# TP_Integrador_Palomino_Villafane_Manuel_.net
KiCad netlist of a schematic drawn in Altium Designer
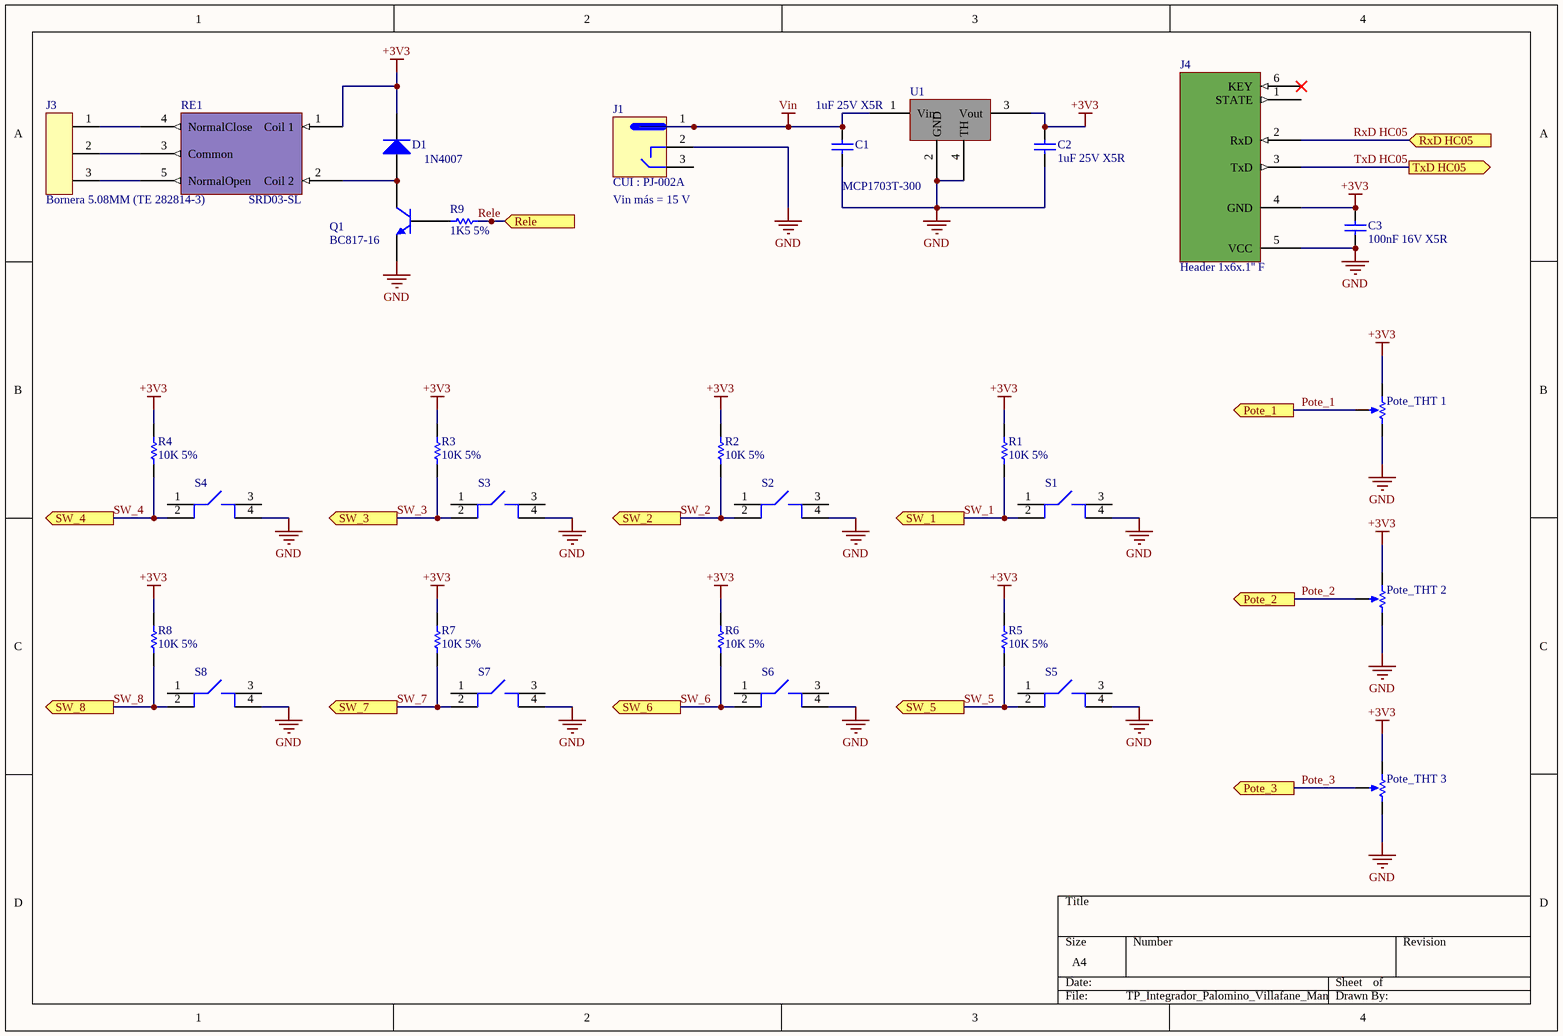
[diagram p0: TP_Integrador_Palomino_Villafane_Manuel_Per_R00.SchDoc]

(export (version "E")
  (design (tool "Eeschema 10.0.6"))
  (components
    (comp (ref "C1")
      (value "1uF 25V X5R")
      (footprint "C_0805")
      (description "Capacitor")
      (libsource (lib "Simulation Generic Components") (part "Capacitor"))
    )
    (comp (ref "C2")
      (value "1uF 25V X5R")
      (footprint "C_0805")
      (description "Capacitor")
      (libsource (lib "Simulation Generic Components") (part "Capacitor"))
    )
    (comp (ref "C3")
      (value "100nF 16V X5R")
      (footprint "C_0805")
      (description "Capacitor")
      (libsource (lib "Simulation Generic Components") (part "Capacitor"))
    )
    (comp (ref "D1")
      (value "1N4007")
      (footprint "SOD_123")
      (description "Diode")
      (libsource (lib "Simulation Generic Components") (part "Diode"))
    )
    (comp (ref "J1")
      (value "CUI : PJ-002A")
      (footprint "PJ002B")
      (description "DC Power Jack")
      (libsource (lib "Base_board_LPC845_R00") (part "PowerInput"))
    )
    (comp (ref "J3")
      (value "Bornera 5.08MM (TE 282814-3)")
      (footprint "BORNERA-3X 5.08MM")
      (description "Header")
      (libsource (lib "Base_board_LPC845_R00") (part "Header 1x3"))
    )
    (comp (ref "J4")
      (value "Header 1x6x.1'' F")
      (footprint "HEADER F 1x6 .1\" Horizintal")
      (description "Bluetooth")
      (libsource (lib "Base_board_LPC845_R00") (part "HC05"))
    )
    (comp (ref "Pote_THT 1")
      (value "Potentiometer")
      (footprint "POTE_9.5MM_PTV09")
      (libsource (lib "Simulation Generic Components") (part "Potentiometer"))
    )
    (comp (ref "Pote_THT 2")
      (value "Potentiometer")
      (footprint "POTE_9.5MM_PTV09")
      (libsource (lib "Simulation Generic Components") (part "Potentiometer"))
    )
    (comp (ref "Pote_THT 3")
      (value "Potentiometer")
      (footprint "POTE_9.5MM_PTV09")
      (libsource (lib "Simulation Generic Components") (part "Potentiometer"))
    )
    (comp (ref "Q1")
      (value "BC817-16")
      (footprint "SOT_23")
      (description "Bipolar NPN 3 Pins Transistor VBIC Model")
      (libsource (lib "Base_board_LPC845_R00") (part "BJT NPN VBIC"))
    )
    (comp (ref "R1")
      (value "10K 5%")
      (footprint "R_0805")
      (description "Resistor")
      (fields (field (name "Comment") "1K3 5%"))
      (libsource (lib "Simulation Generic Components") (part "Resistor"))
    )
    (comp (ref "R2")
      (value "10K 5%")
      (footprint "R_0805")
      (description "Resistor")
      (fields (field (name "Comment") "1K3 5%"))
      (libsource (lib "Simulation Generic Components") (part "Resistor"))
    )
    (comp (ref "R3")
      (value "10K 5%")
      (footprint "R_0805")
      (description "Resistor")
      (fields (field (name "Comment") "1K3 5%"))
      (libsource (lib "Simulation Generic Components") (part "Resistor"))
    )
    (comp (ref "R4")
      (value "10K 5%")
      (footprint "R_0805")
      (description "Resistor")
      (fields (field (name "Comment") "1K3 5%"))
      (libsource (lib "Simulation Generic Components") (part "Resistor"))
    )
    (comp (ref "R5")
      (value "10K 5%")
      (footprint "R_0805")
      (description "Resistor")
      (fields (field (name "Comment") "1K3 5%"))
      (libsource (lib "Simulation Generic Components") (part "Resistor"))
    )
    (comp (ref "R6")
      (value "10K 5%")
      (footprint "R_0805")
      (description "Resistor")
      (fields (field (name "Comment") "1K3 5%"))
      (libsource (lib "Simulation Generic Components") (part "Resistor"))
    )
    (comp (ref "R7")
      (value "10K 5%")
      (footprint "R_0805")
      (description "Resistor")
      (fields (field (name "Comment") "1K3 5%"))
      (libsource (lib "Simulation Generic Components") (part "Resistor"))
    )
    (comp (ref "R8")
      (value "10K 5%")
      (footprint "R_0805")
      (description "Resistor")
      (fields (field (name "Comment") "1K3 5%"))
      (libsource (lib "Simulation Generic Components") (part "Resistor"))
    )
    (comp (ref "R9")
      (value "Resistor")
      (footprint "R_0805")
      (fields (field (name "1K5 5%") "1K5 5%"))
      (libsource (lib "Simulation Generic Components") (part "Resistor"))
    )
    (comp (ref "RE1")
      (value "SRD03-SL")
      (footprint "Relay SRD")
      (description "Relay")
      (libsource (lib "Base_board_LPC845_R00") (part "RELAY"))
    )
    (comp (ref "S1")
      (value "Tact Switch - 430476085716")
      (footprint "Tact_Switch_12x12")
      (description "Tact Switch")
      (libsource (lib "*") (part "TactSwitch"))
    )
    (comp (ref "S2")
      (value "Tact Switch - 430476085716")
      (footprint "Tact_Switch_12x12")
      (description "Tact Switch")
      (libsource (lib "*") (part "TactSwitch"))
    )
    (comp (ref "S3")
      (value "Tact Switch - 430476085716")
      (footprint "Tact_Switch_12x12")
      (description "Tact Switch")
      (libsource (lib "*") (part "TactSwitch"))
    )
    (comp (ref "S4")
      (value "Tact Switch - 430476085716")
      (footprint "Tact_Switch_12x12")
      (description "Tact Switch")
      (libsource (lib "*") (part "TactSwitch"))
    )
    (comp (ref "S5")
      (value "Tact Switch - 430476085716")
      (footprint "Tact_Switch_12x12")
      (description "Tact Switch")
      (libsource (lib "*") (part "TactSwitch"))
    )
    (comp (ref "S6")
      (value "Tact Switch - 430476085716")
      (footprint "Tact_Switch_12x12")
      (description "Tact Switch")
      (libsource (lib "*") (part "TactSwitch"))
    )
    (comp (ref "S7")
      (value "Tact Switch - 430476085716")
      (footprint "Tact_Switch_12x12")
      (description "Tact Switch")
      (libsource (lib "*") (part "TactSwitch"))
    )
    (comp (ref "S8")
      (value "Tact Switch - 430476085716")
      (footprint "Tact_Switch_12x12")
      (description "Tact Switch")
      (libsource (lib "*") (part "TactSwitch"))
    )
    (comp (ref "U1")
      (value "MCP1703T-300")
      (footprint "SOT_223_4L")
      (description "LDO")
      (libsource (lib "Base_board_LPC845_R00") (part "MCP1703"))
    )
  )
  (nets
    (net (code "1") (name "+3V3") (class "Default")
      (node (ref "C2") (pin "2") (pinfunction "2_2") (pintype "passive"))
      (node (ref "C3") (pin "2") (pinfunction "2_2") (pintype "passive"))
      (node (ref "D1") (pin "2") (pinfunction "K_2") (pintype "passive"))
      (node (ref "J4") (pin "4") (pinfunction "GND_4") (pintype "power_in"))
      (node (ref "Pote_THT 1") (pin "1") (pinfunction "TOP_1") (pintype "passive"))
      (node (ref "Pote_THT 2") (pin "1") (pinfunction "TOP_1") (pintype "passive"))
      (node (ref "Pote_THT 3") (pin "1") (pinfunction "TOP_1") (pintype "passive"))
      (node (ref "R1") (pin "2") (pinfunction "2_2") (pintype "passive"))
      (node (ref "R2") (pin "2") (pinfunction "2_2") (pintype "passive"))
      (node (ref "R3") (pin "2") (pinfunction "2_2") (pintype "passive"))
      (node (ref "R4") (pin "2") (pinfunction "2_2") (pintype "passive"))
      (node (ref "R5") (pin "2") (pinfunction "2_2") (pintype "passive"))
      (node (ref "R6") (pin "2") (pinfunction "2_2") (pintype "passive"))
      (node (ref "R7") (pin "2") (pinfunction "2_2") (pintype "passive"))
      (node (ref "R8") (pin "2") (pinfunction "2_2") (pintype "passive"))
      (node (ref "RE1") (pin "1") (pinfunction "Coil_1_1") (pintype "input"))
      (node (ref "U1") (pin "3") (pinfunction "Vout_3") (pintype "power_in"))
    )
    (net (code "2") (name "/Pote_1") (class "Default")
      (node (ref "Pote_THT 1") (pin "3") (pinfunction "TAP_3") (pintype "passive"))
    )
    (net (code "3") (name "/Pote_2") (class "Default")
      (node (ref "Pote_THT 2") (pin "3") (pinfunction "TAP_3") (pintype "passive"))
    )
    (net (code "4") (name "/Pote_3") (class "Default")
      (node (ref "Pote_THT 3") (pin "3") (pinfunction "TAP_3") (pintype "passive"))
    )
    (net (code "5") (name "/Rele") (class "Default")
      (node (ref "R9") (pin "2") (pinfunction "2_2") (pintype "passive"))
    )
    (net (code "6") (name "/RxD HC05") (class "Default")
      (node (ref "J4") (pin "2") (pinfunction "RxD_2") (pintype "input"))
    )
    (net (code "7") (name "/SW_1") (class "Default")
      (node (ref "R1") (pin "1") (pinfunction "1_1") (pintype "passive"))
      (node (ref "S1") (pin "2") (pinfunction "2_2") (pintype "passive"))
    )
    (net (code "8") (name "/SW_2") (class "Default")
      (node (ref "R2") (pin "1") (pinfunction "1_1") (pintype "passive"))
      (node (ref "S2") (pin "2") (pinfunction "2_2") (pintype "passive"))
    )
    (net (code "9") (name "/SW_3") (class "Default")
      (node (ref "R3") (pin "1") (pinfunction "1_1") (pintype "passive"))
      (node (ref "S3") (pin "2") (pinfunction "2_2") (pintype "passive"))
    )
    (net (code "10") (name "/SW_4") (class "Default")
      (node (ref "R4") (pin "1") (pinfunction "1_1") (pintype "passive"))
      (node (ref "S4") (pin "2") (pinfunction "2_2") (pintype "passive"))
    )
    (net (code "11") (name "/SW_5") (class "Default")
      (node (ref "R5") (pin "1") (pinfunction "1_1") (pintype "passive"))
      (node (ref "S5") (pin "2") (pinfunction "2_2") (pintype "passive"))
    )
    (net (code "12") (name "/SW_6") (class "Default")
      (node (ref "R6") (pin "1") (pinfunction "1_1") (pintype "passive"))
      (node (ref "S6") (pin "2") (pinfunction "2_2") (pintype "passive"))
    )
    (net (code "13") (name "/SW_7") (class "Default")
      (node (ref "R7") (pin "1") (pinfunction "1_1") (pintype "passive"))
      (node (ref "S7") (pin "2") (pinfunction "2_2") (pintype "passive"))
    )
    (net (code "14") (name "/SW_8") (class "Default")
      (node (ref "R8") (pin "1") (pinfunction "1_1") (pintype "passive"))
      (node (ref "S8") (pin "2") (pinfunction "2_2") (pintype "passive"))
    )
    (net (code "15") (name "/TxD HC05") (class "Default")
      (node (ref "J4") (pin "3") (pinfunction "TxD_3") (pintype "output"))
    )
    (net (code "16") (name "GND") (class "Default")
      (node (ref "C1") (pin "1") (pinfunction "1_1") (pintype "passive"))
      (node (ref "C2") (pin "1") (pinfunction "1_1") (pintype "passive"))
      (node (ref "C3") (pin "1") (pinfunction "1_1") (pintype "passive"))
      (node (ref "J1") (pin "2") (pinfunction "2_2") (pintype "passive"))
      (node (ref "J4") (pin "5") (pinfunction "VCC_5") (pintype "power_in"))
      (node (ref "Pote_THT 1") (pin "2") (pinfunction "BOT_2") (pintype "passive"))
      (node (ref "Pote_THT 2") (pin "2") (pinfunction "BOT_2") (pintype "passive"))
      (node (ref "Pote_THT 3") (pin "2") (pinfunction "BOT_2") (pintype "passive"))
      (node (ref "Q1") (pin "2") (pinfunction "E_2") (pintype "passive"))
      (node (ref "S1") (pin "4") (pinfunction "4_4") (pintype "passive"))
      (node (ref "S2") (pin "4") (pinfunction "4_4") (pintype "passive"))
      (node (ref "S3") (pin "4") (pinfunction "4_4") (pintype "passive"))
      (node (ref "S4") (pin "4") (pinfunction "4_4") (pintype "passive"))
      (node (ref "S5") (pin "4") (pinfunction "4_4") (pintype "passive"))
      (node (ref "S6") (pin "4") (pinfunction "4_4") (pintype "passive"))
      (node (ref "S7") (pin "4") (pinfunction "4_4") (pintype "passive"))
      (node (ref "S8") (pin "4") (pinfunction "4_4") (pintype "passive"))
      (node (ref "U1") (pin "2") (pinfunction "GND_2") (pintype "power_in"))
      (node (ref "U1") (pin "4") (pinfunction "TH_4") (pintype "passive"))
    )
    (net (code "17") (name "Net-(D1-A)") (class "Default")
      (node (ref "D1") (pin "1") (pinfunction "A_1") (pintype "passive"))
      (node (ref "Q1") (pin "3") (pinfunction "C_3") (pintype "passive"))
      (node (ref "RE1") (pin "2") (pinfunction "Coil_2_2") (pintype "input"))
    )
    (net (code "18") (name "Net-(Q1-B)") (class "Default")
      (node (ref "Q1") (pin "1") (pinfunction "B_1") (pintype "passive"))
      (node (ref "R9") (pin "1") (pinfunction "1_1") (pintype "passive"))
    )
    (net (code "19") (name "Net-(RE1-Common)") (class "Default")
      (node (ref "J3") (pin "2") (pinfunction "2_2") (pintype "passive"))
      (node (ref "RE1") (pin "3") (pinfunction "Common_3") (pintype "output"))
    )
    (net (code "20") (name "Net-(RE1-NormalClose)") (class "Default")
      (node (ref "J3") (pin "1") (pinfunction "1_1") (pintype "passive"))
      (node (ref "RE1") (pin "4") (pinfunction "NormalClose_4") (pintype "output"))
    )
    (net (code "21") (name "Net-(RE1-NormalOpen)") (class "Default")
      (node (ref "J3") (pin "3") (pinfunction "3_3") (pintype "passive"))
      (node (ref "RE1") (pin "5") (pinfunction "NormalOpen_5") (pintype "output"))
    )
    (net (code "22") (name "Vin") (class "Default")
      (node (ref "C1") (pin "2") (pinfunction "2_2") (pintype "passive"))
      (node (ref "J1") (pin "1") (pinfunction "1_1") (pintype "passive"))
      (node (ref "U1") (pin "1") (pinfunction "Vin_1") (pintype "power_in"))
    )
    (net (code "23") (name "unconnected-(J1-Pad3)") (class "Default")
      (node (ref "J1") (pin "3") (pinfunction "3_3") (pintype "passive"))
    )
    (net (code "24") (name "unconnected-(J4-KEY-Pad6)") (class "Default")
      (node (ref "J4") (pin "6") (pinfunction "KEY_6") (pintype "input+no_connect"))
    )
    (net (code "25") (name "unconnected-(J4-STATE-Pad1)") (class "Default")
      (node (ref "J4") (pin "1") (pinfunction "STATE_1") (pintype "output"))
    )
    (net (code "26") (name "unconnected-(S1-Pad1)") (class "Default")
      (node (ref "S1") (pin "1") (pinfunction "1_1") (pintype "passive"))
    )
    (net (code "27") (name "unconnected-(S1-Pad3)") (class "Default")
      (node (ref "S1") (pin "3") (pinfunction "3_3") (pintype "passive"))
    )
    (net (code "28") (name "unconnected-(S2-Pad1)") (class "Default")
      (node (ref "S2") (pin "1") (pinfunction "1_1") (pintype "passive"))
    )
    (net (code "29") (name "unconnected-(S2-Pad3)") (class "Default")
      (node (ref "S2") (pin "3") (pinfunction "3_3") (pintype "passive"))
    )
    (net (code "30") (name "unconnected-(S3-Pad1)") (class "Default")
      (node (ref "S3") (pin "1") (pinfunction "1_1") (pintype "passive"))
    )
    (net (code "31") (name "unconnected-(S3-Pad3)") (class "Default")
      (node (ref "S3") (pin "3") (pinfunction "3_3") (pintype "passive"))
    )
    (net (code "32") (name "unconnected-(S4-Pad1)") (class "Default")
      (node (ref "S4") (pin "1") (pinfunction "1_1") (pintype "passive"))
    )
    (net (code "33") (name "unconnected-(S4-Pad3)") (class "Default")
      (node (ref "S4") (pin "3") (pinfunction "3_3") (pintype "passive"))
    )
    (net (code "34") (name "unconnected-(S5-Pad1)") (class "Default")
      (node (ref "S5") (pin "1") (pinfunction "1_1") (pintype "passive"))
    )
    (net (code "35") (name "unconnected-(S5-Pad3)") (class "Default")
      (node (ref "S5") (pin "3") (pinfunction "3_3") (pintype "passive"))
    )
    (net (code "36") (name "unconnected-(S6-Pad1)") (class "Default")
      (node (ref "S6") (pin "1") (pinfunction "1_1") (pintype "passive"))
    )
    (net (code "37") (name "unconnected-(S6-Pad3)") (class "Default")
      (node (ref "S6") (pin "3") (pinfunction "3_3") (pintype "passive"))
    )
    (net (code "38") (name "unconnected-(S7-Pad1)") (class "Default")
      (node (ref "S7") (pin "1") (pinfunction "1_1") (pintype "passive"))
    )
    (net (code "39") (name "unconnected-(S7-Pad3)") (class "Default")
      (node (ref "S7") (pin "3") (pinfunction "3_3") (pintype "passive"))
    )
    (net (code "40") (name "unconnected-(S8-Pad1)") (class "Default")
      (node (ref "S8") (pin "1") (pinfunction "1_1") (pintype "passive"))
    )
    (net (code "41") (name "unconnected-(S8-Pad3)") (class "Default")
      (node (ref "S8") (pin "3") (pinfunction "3_3") (pintype "passive"))
    )
  )
)
